# t1-power3.net
KiCad netlist of a schematic drawn in Altium Designer
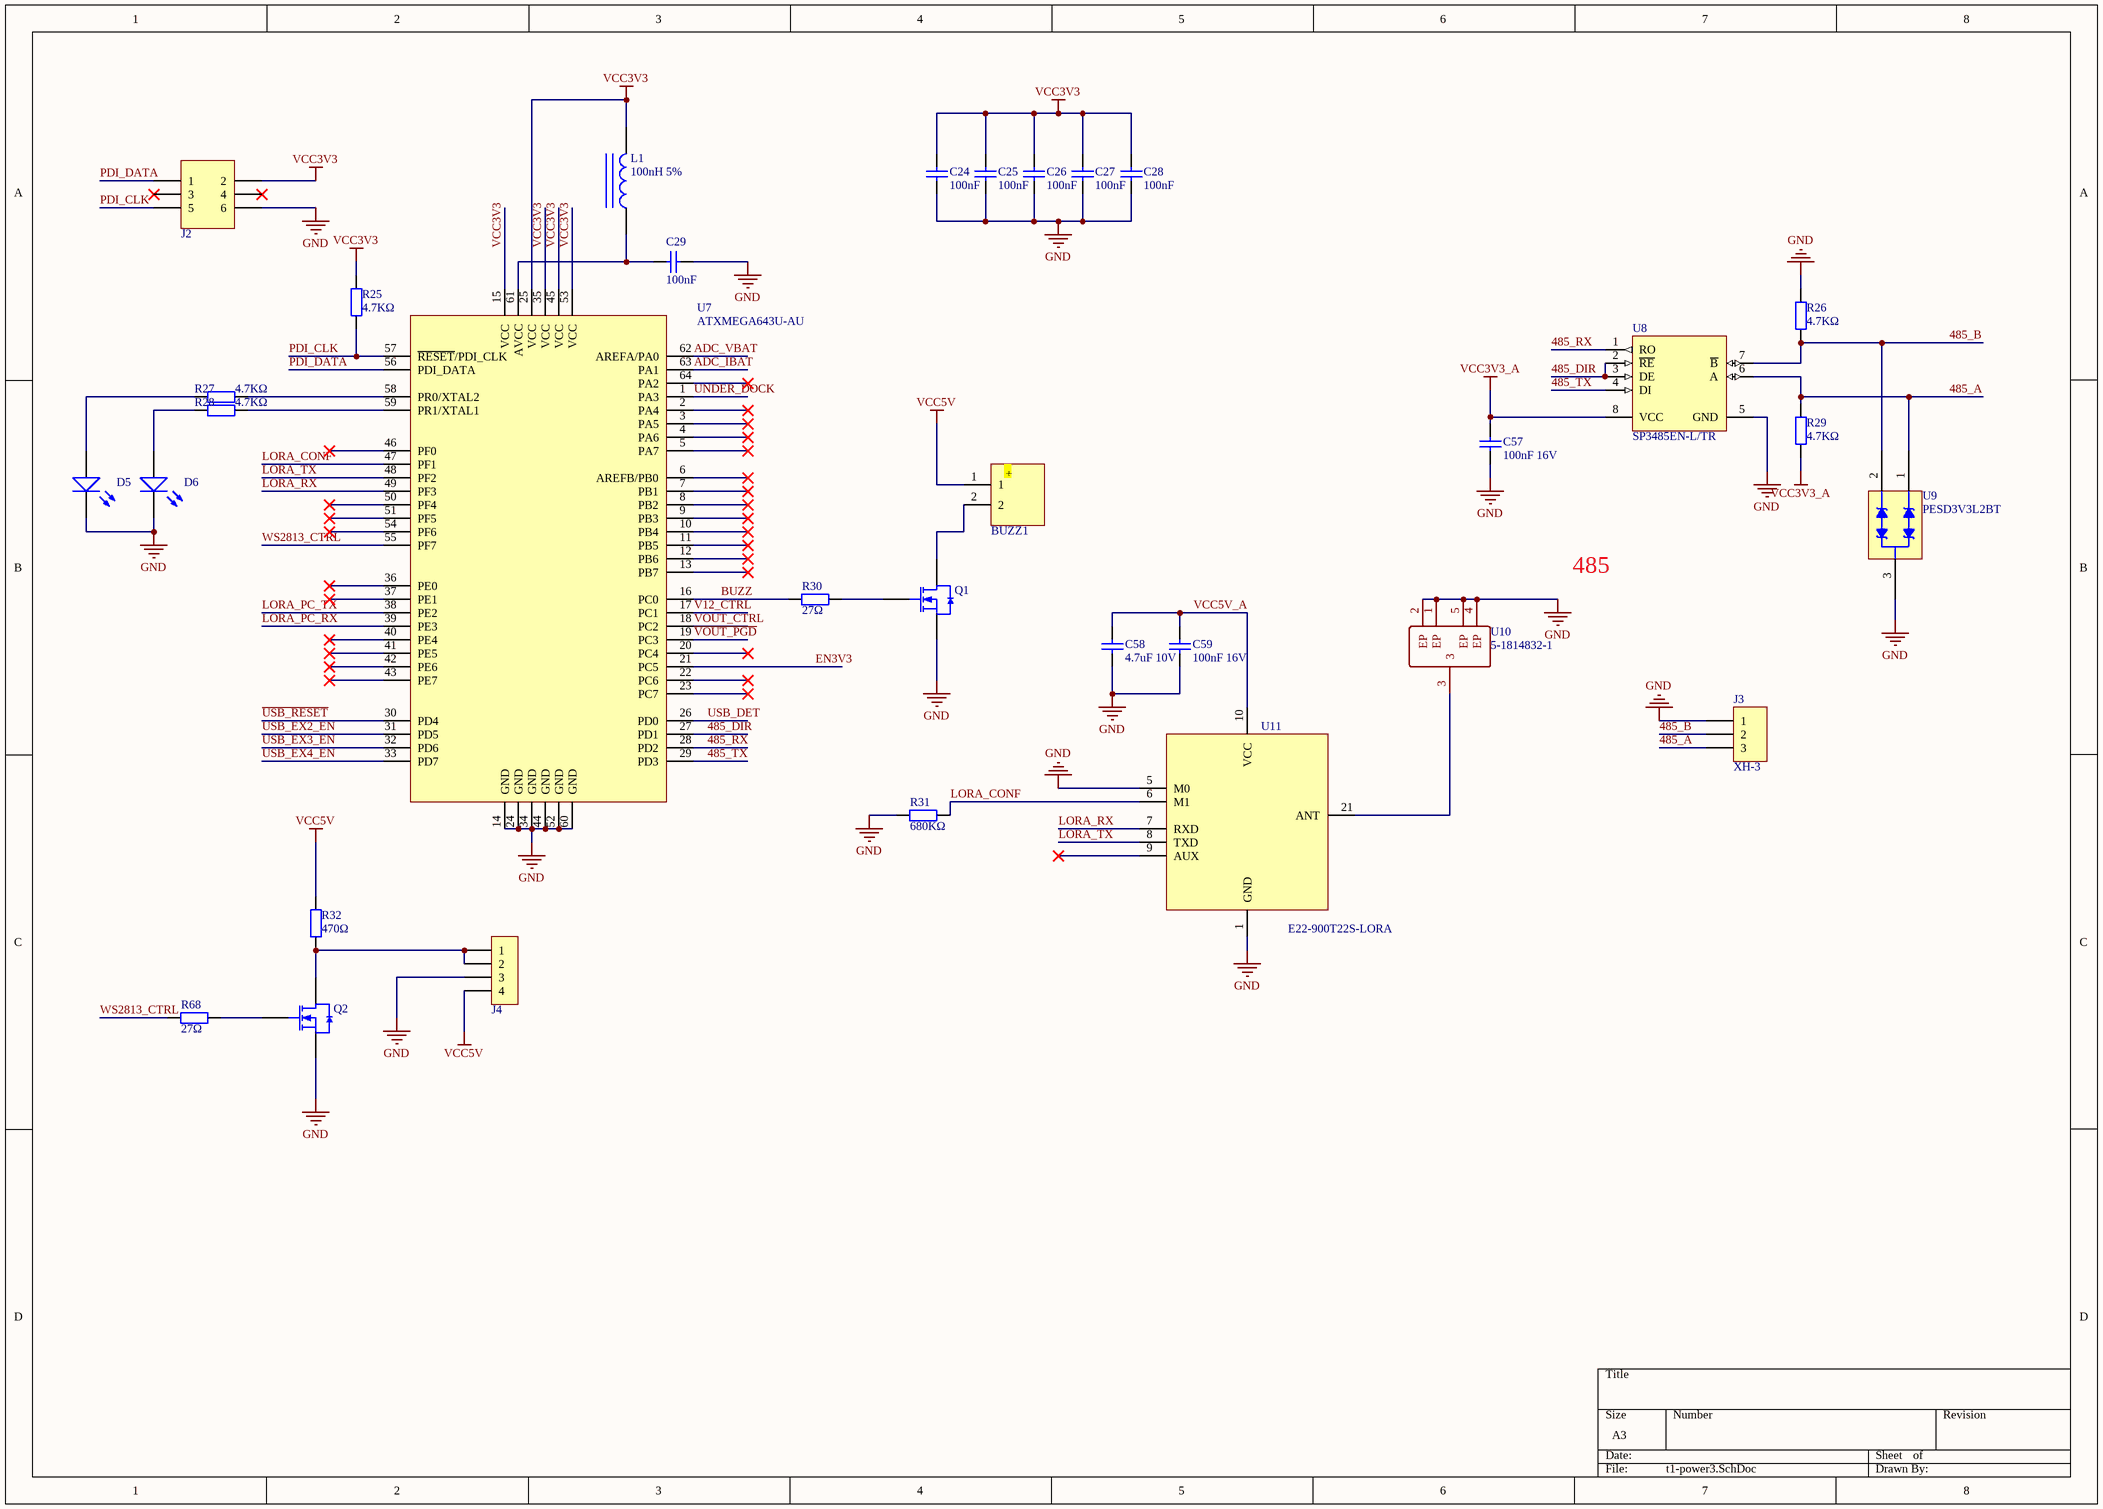
[diagram p0: t1-power3.SchDoc]

(export (version "E")
  (design (tool "Eeschema 10.0.6"))
  (components
    (comp (ref "BUZZ1") (value "B?") (footprint "直插5.0_9*5.5mm") (libsource (lib "我的原理图库") (part "BUZZ")))
    (comp (ref "C24")
      (value "100nF")
      (footprint "0402_C")
      (description "贴片电容")
      (libsource (lib "AD封装2018.9.19Miscellaneous Devices LC") (part "0402 100nF (104) 10% 16V"))
    )
    (comp (ref "C25")
      (value "100nF")
      (footprint "0402_C")
      (description "贴片电容")
      (libsource (lib "AD封装2018.9.19Miscellaneous Devices LC") (part "0402 100nF (104) 10% 16V"))
    )
    (comp (ref "C26")
      (value "100nF")
      (footprint "0402_C")
      (description "贴片电容")
      (libsource (lib "AD封装2018.9.19Miscellaneous Devices LC") (part "0402 100nF (104) 10% 16V"))
    )
    (comp (ref "C27")
      (value "100nF")
      (footprint "0402_C")
      (description "贴片电容")
      (libsource (lib "AD封装2018.9.19Miscellaneous Devices LC") (part "0402 100nF (104) 10% 16V"))
    )
    (comp (ref "C28")
      (value "100nF")
      (footprint "0402_C")
      (description "贴片电容")
      (libsource (lib "AD封装2018.9.19Miscellaneous Devices LC") (part "0402 100nF (104) 10% 16V"))
    )
    (comp (ref "C29")
      (value "100nF")
      (footprint "0402_C")
      (description "贴片电容")
      (libsource (lib "AD封装2018.9.19Miscellaneous Devices LC") (part "0402 100nF (104) 10% 16V"))
    )
    (comp (ref "C57")
      (value "100nF 16V")
      (footprint "0402_C")
      (description "贴片电容")
      (libsource (lib "AD封装2018.9.19Miscellaneous Devices LC") (part "0402 100nF (104) 10% 16V"))
    )
    (comp (ref "C58")
      (value "4.7uF 10V")
      (footprint "0402_C")
      (description "贴片电容")
      (libsource (lib "AD封装2018.9.19Miscellaneous Devices LC") (part "0402 4.7uF (475) 20% 10V"))
    )
    (comp (ref "C59")
      (value "100nF 16V")
      (footprint "0402_C")
      (description "贴片电容")
      (libsource (lib "AD封装2018.9.19Miscellaneous Devices LC") (part "0402 100nF (104) 10% 16V"))
    )
    (comp (ref "D5")
      (value "白灯 0603")
      (footprint "0603_LED_S1")
      (description "发光二极管")
      (libsource (lib "AD封装2018.9.19Miscellaneous Devices LC") (part "0603 白灯"))
    )
    (comp (ref "D6")
      (value "白灯 0603")
      (footprint "0603_LED_S1")
      (description "发光二极管")
      (libsource (lib "AD封装2018.9.19Miscellaneous Devices LC") (part "0603 白灯"))
    )
    (comp (ref "J2")
      (value "Conn_02*03_2.54mm")
      (footprint "排针2.54mm")
      (libsource (lib "我的集成库") (part "Conn_02*03_2.54mm"))
    )
    (comp (ref "J3") (value "XH-3") (footprint "ph3-2.0") (libsource (lib "我的原理图库") (part "XH-3")))
    (comp (ref "J4") (value "header4") (footprint "xh-4") (libsource (lib "我的集成库") (part "header4")))
    (comp (ref "L1")
      (value "100nH 5%")
      (footprint "0402_L")
      (description "贴片电感")
      (libsource (lib "AD封装2018.9.19Miscellaneous Devices LC") (part "0402 10nH 5%"))
    )
    (comp (ref "Q1")
      (value "AO3400A N道沟 X0YV1T SOT-23")
      (footprint "SOT-23-3L")
      (description "MOS(场效应管)")
      (libsource (lib "AD封装2018.9.19Miscellaneous Devices LC") (part "AO3400A N道沟 X0YV1T SOT-23"))
    )
    (comp (ref "Q2")
      (value "AO3400A N道沟 X0YV1T SOT-23")
      (footprint "SOT-23-3L")
      (description "MOS(场效应管)")
      (libsource (lib "AD封装2018.9.19Miscellaneous Devices LC") (part "AO3400A N道沟 X0YV1T SOT-23"))
    )
    (comp (ref "R25")
      (value "4.7KΩ")
      (footprint "0402_R")
      (description "贴片电阻")
      (libsource (lib "AD封装2018.9.19Miscellaneous Devices LC") (part "0402 4.7KΩ (4701) 1%"))
    )
    (comp (ref "R26")
      (value "4.7KΩ")
      (footprint "0402_R")
      (description "贴片电阻")
      (libsource (lib "AD封装2018.9.19Miscellaneous Devices LC") (part "0402 4.7KΩ (4701) 1%"))
    )
    (comp (ref "R27")
      (value "4.7KΩ")
      (footprint "0402_R")
      (description "贴片电阻")
      (libsource (lib "") (part "0402 4.7KΩ (4701) 1%_1"))
    )
    (comp (ref "R28")
      (value "4.7KΩ")
      (footprint "0402_R")
      (description "贴片电阻")
      (libsource (lib "") (part "0402 4.7KΩ (4701) 1%_1"))
    )
    (comp (ref "R29")
      (value "4.7KΩ")
      (footprint "0402_R")
      (description "贴片电阻")
      (libsource (lib "AD封装2018.9.19Miscellaneous Devices LC") (part "0402 4.7KΩ (4701) 1%"))
    )
    (comp (ref "R30")
      (value "27Ω")
      (footprint "0402_R")
      (description "贴片电阻")
      (libsource (lib "AD封装2018.9.19Miscellaneous Devices LC") (part "0402 27KΩ (2702) 1%"))
    )
    (comp (ref "R31")
      (value "680KΩ")
      (footprint "0402_R")
      (description "贴片电阻")
      (libsource (lib "AD封装2018.9.19Miscellaneous Devices LC") (part "0402 680Ω (6800) 1%"))
    )
    (comp (ref "R32")
      (value "470Ω")
      (footprint "0402_R")
      (description "贴片电阻")
      (libsource (lib "AD封装2018.9.19Miscellaneous Devices LC") (part "0402 470Ω (4700) 1%"))
    )
    (comp (ref "R68")
      (value "27Ω")
      (footprint "0402_R")
      (description "贴片电阻")
      (libsource (lib "AD封装2018.9.19Miscellaneous Devices LC") (part "0402 27KΩ (2702) 1%"))
    )
    (comp (ref "U7")
      (value "ATXMEGA643U-AU")
      (footprint "TQFP-64_14*14*08P")
      (description "TFQP-64")
      (libsource (lib "我的原理图库") (part "atxmage64a3u"))
    )
    (comp (ref "U8")
      (value "SP3485EN-L/TR")
      (footprint "SOIC-8_150mil")
      (description "RS-485/RS-422")
      (libsource (lib "IC") (part "SP3485EN-L/TR_[C8963]"))
    )
    (comp (ref "U9")
      (value "PESD3V3L2BT")
      (footprint "SOT-23(SOT-23-3)")
      (description "TVS")
      (libsource (lib "AD封装2018.9.19Miscellaneous Devices LC") (part "PSM712-LF-T7_[C32677]"))
    )
    (comp (ref "U10")
      (value "5-1814832-1")
      (footprint "SMA 连接器")
      (libsource (lib "我的集成库") (part "5-1814832-1"))
    )
    (comp (ref "U11")
      (value "E22-900T22S-LORA")
      (footprint "LORA-16mmX26mm")
      (libsource (lib "我的集成库") (part "E22-900T22S-LORA"))
    )
  )
  (nets
    (net (code "1") (name "/485_A") (class "Default")
      (node (ref "J3") (pin "3") (pinfunction "3_3") (pintype "passive"))
      (node (ref "R29") (pin "2") (pinfunction "2_2") (pintype "passive"))
      (node (ref "U8") (pin "6") (pinfunction "A_6") (pintype "bidirectional"))
      (node (ref "U9") (pin "1") (pinfunction "1_1") (pintype "passive"))
    )
    (net (code "2") (name "/485_B") (class "Default")
      (node (ref "J3") (pin "2") (pinfunction "2_2") (pintype "passive"))
      (node (ref "R26") (pin "1") (pinfunction "1_1") (pintype "passive"))
      (node (ref "U8") (pin "7") (pinfunction "~{B}_7") (pintype "bidirectional"))
      (node (ref "U9") (pin "2") (pinfunction "2_2") (pintype "passive"))
    )
    (net (code "3") (name "/485_DIR") (class "Default")
      (node (ref "U7") (pin "27") (pinfunction "PD1_27") (pintype "passive"))
      (node (ref "U8") (pin "2") (pinfunction "~{RE}_2") (pintype "input"))
      (node (ref "U8") (pin "3") (pinfunction "DE_3") (pintype "input"))
    )
    (net (code "4") (name "/485_RX") (class "Default")
      (node (ref "U7") (pin "28") (pinfunction "PD2_28") (pintype "passive"))
      (node (ref "U8") (pin "1") (pinfunction "RO_1") (pintype "output"))
    )
    (net (code "5") (name "/485_TX") (class "Default")
      (node (ref "U7") (pin "29") (pinfunction "PD3_29") (pintype "passive"))
      (node (ref "U8") (pin "4") (pinfunction "DI_4") (pintype "input"))
    )
    (net (code "6") (name "/ADC_IBAT") (class "Default")
      (node (ref "U7") (pin "63") (pinfunction "PA1_63") (pintype "passive"))
    )
    (net (code "7") (name "/ADC_VBAT") (class "Default")
      (node (ref "U7") (pin "62") (pinfunction "AREFA/PA0_62") (pintype "passive"))
    )
    (net (code "8") (name "/BUZZ") (class "Default")
      (node (ref "R30") (pin "1") (pinfunction "1_1") (pintype "passive"))
      (node (ref "U7") (pin "16") (pinfunction "PC0_16") (pintype "passive"))
    )
    (net (code "9") (name "/EN3V3") (class "Default")
      (node (ref "U7") (pin "21") (pinfunction "PC5_21") (pintype "passive"))
    )
    (net (code "10") (name "/LORA_CONF") (class "Default")
      (node (ref "R31") (pin "2") (pinfunction "2_2") (pintype "passive"))
      (node (ref "U11") (pin "6") (pinfunction "M1_6") (pintype "passive"))
      (node (ref "U7") (pin "47") (pinfunction "PF1_47") (pintype "passive"))
    )
    (net (code "11") (name "/LORA_PC_RX") (class "Default")
      (node (ref "U7") (pin "39") (pinfunction "PE3_39") (pintype "passive"))
    )
    (net (code "12") (name "/LORA_PC_TX") (class "Default")
      (node (ref "U7") (pin "38") (pinfunction "PE2_38") (pintype "passive"))
    )
    (net (code "13") (name "/LORA_RX") (class "Default")
      (node (ref "U11") (pin "7") (pinfunction "RXD_7") (pintype "passive"))
      (node (ref "U7") (pin "49") (pinfunction "PF3_49") (pintype "passive"))
    )
    (net (code "14") (name "/LORA_TX") (class "Default")
      (node (ref "U11") (pin "8") (pinfunction "TXD_8") (pintype "passive"))
      (node (ref "U7") (pin "48") (pinfunction "PF2_48") (pintype "passive"))
    )
    (net (code "15") (name "/PDI_CLK") (class "Default")
      (node (ref "J2") (pin "5") (pinfunction "5_5") (pintype "passive"))
      (node (ref "R25") (pin "1") (pinfunction "1_1") (pintype "passive"))
      (node (ref "U7") (pin "57") (pinfunction "~{RESET}/PDI_CLK_57") (pintype "passive"))
    )
    (net (code "16") (name "/PDI_DATA") (class "Default")
      (node (ref "J2") (pin "1") (pinfunction "1_1") (pintype "passive"))
      (node (ref "U7") (pin "56") (pinfunction "PDI_DATA_56") (pintype "passive"))
    )
    (net (code "17") (name "/UNDER_DOCK") (class "Default")
      (node (ref "U7") (pin "1") (pinfunction "PA3_1") (pintype "passive"))
    )
    (net (code "18") (name "/USB_DET") (class "Default")
      (node (ref "U7") (pin "26") (pinfunction "PD0_26") (pintype "passive"))
    )
    (net (code "19") (name "/USB_EX2_EN") (class "Default")
      (node (ref "U7") (pin "31") (pinfunction "PD5_31") (pintype "passive"))
    )
    (net (code "20") (name "/USB_EX3_EN") (class "Default")
      (node (ref "U7") (pin "32") (pinfunction "PD6_32") (pintype "passive"))
    )
    (net (code "21") (name "/USB_EX4_EN") (class "Default")
      (node (ref "U7") (pin "33") (pinfunction "PD7_33") (pintype "passive"))
    )
    (net (code "22") (name "/V12_CTRL") (class "Default")
      (node (ref "U7") (pin "17") (pinfunction "PC1_17") (pintype "passive"))
    )
    (net (code "23") (name "/VCC5V_A") (class "Default")
      (node (ref "C58") (pin "2") (pinfunction "2_2") (pintype "passive"))
      (node (ref "C59") (pin "2") (pinfunction "2_2") (pintype "passive"))
      (node (ref "U11") (pin "10") (pinfunction "VCC_10") (pintype "passive"))
    )
    (net (code "24") (name "/VOUT_CTRL") (class "Default")
      (node (ref "U7") (pin "18") (pinfunction "PC2_18") (pintype "passive"))
    )
    (net (code "25") (name "/WS2813_CTRL") (class "Default")
      (node (ref "R68") (pin "1") (pinfunction "1_1") (pintype "passive"))
      (node (ref "U7") (pin "55") (pinfunction "PF7_55") (pintype "passive"))
    )
    (net (code "26") (name "/~{USB_RESET}") (class "Default")
      (node (ref "U7") (pin "30") (pinfunction "PD4_30") (pintype "passive"))
    )
    (net (code "27") (name "/~{VOUT_PGD}") (class "Default")
      (node (ref "U7") (pin "19") (pinfunction "PC3_19") (pintype "passive"))
    )
    (net (code "28") (name "GND") (class "Default")
      (node (ref "C24") (pin "1") (pinfunction "1_1") (pintype "passive"))
      (node (ref "C25") (pin "1") (pinfunction "1_1") (pintype "passive"))
      (node (ref "C26") (pin "1") (pinfunction "1_1") (pintype "passive"))
      (node (ref "C27") (pin "1") (pinfunction "1_1") (pintype "passive"))
      (node (ref "C28") (pin "1") (pinfunction "1_1") (pintype "passive"))
      (node (ref "C29") (pin "2") (pinfunction "2_2") (pintype "passive"))
      (node (ref "C57") (pin "1") (pinfunction "1_1") (pintype "passive"))
      (node (ref "C58") (pin "1") (pinfunction "1_1") (pintype "passive"))
      (node (ref "C59") (pin "1") (pinfunction "1_1") (pintype "passive"))
      (node (ref "D5") (pin "K") (pinfunction "K_K") (pintype "passive"))
      (node (ref "D6") (pin "K") (pinfunction "K_K") (pintype "passive"))
      (node (ref "J2") (pin "6") (pinfunction "6_6") (pintype "passive"))
      (node (ref "J3") (pin "1") (pinfunction "1_1") (pintype "passive"))
      (node (ref "J4") (pin "3") (pinfunction "3_3") (pintype "passive"))
      (node (ref "Q1") (pin "2") (pinfunction "S_2") (pintype "passive"))
      (node (ref "Q2") (pin "2") (pinfunction "S_2") (pintype "passive"))
      (node (ref "R26") (pin "2") (pinfunction "2_2") (pintype "passive"))
      (node (ref "R31") (pin "1") (pinfunction "1_1") (pintype "passive"))
      (node (ref "U10") (pin "1") (pinfunction "EP_1") (pintype "passive"))
      (node (ref "U10") (pin "2") (pinfunction "EP_2") (pintype "passive"))
      (node (ref "U10") (pin "4") (pinfunction "EP_4") (pintype "passive"))
      (node (ref "U10") (pin "5") (pinfunction "EP_5") (pintype "passive"))
      (node (ref "U11") (pin "1") (pinfunction "GND_1") (pintype "passive"))
      (node (ref "U11") (pin "5") (pinfunction "M0_5") (pintype "passive"))
      (node (ref "U7") (pin "14") (pinfunction "GND_14") (pintype "passive"))
      (node (ref "U7") (pin "24") (pinfunction "GND_24") (pintype "passive"))
      (node (ref "U7") (pin "34") (pinfunction "GND_34") (pintype "passive"))
      (node (ref "U7") (pin "44") (pinfunction "GND_44") (pintype "passive"))
      (node (ref "U7") (pin "52") (pinfunction "GND_52") (pintype "passive"))
      (node (ref "U7") (pin "60") (pinfunction "GND_60") (pintype "passive"))
      (node (ref "U8") (pin "5") (pinfunction "GND_5") (pintype "power_in"))
      (node (ref "U9") (pin "3") (pinfunction "3_3") (pintype "passive"))
    )
    (net (code "29") (name "Net-(D5-PadA)") (class "Default")
      (node (ref "D5") (pin "A") (pinfunction "A_A") (pintype "passive"))
      (node (ref "R27") (pin "1") (pinfunction "1_1") (pintype "passive"))
    )
    (net (code "30") (name "Net-(D6-PadA)") (class "Default")
      (node (ref "D6") (pin "A") (pinfunction "A_A") (pintype "passive"))
      (node (ref "R28") (pin "1") (pinfunction "1_1") (pintype "passive"))
    )
    (net (code "31") (name "Net-(Q1-D)") (class "Default")
      (node (ref "BUZZ1") (pin "2") (pinfunction "2_2") (pintype "passive"))
      (node (ref "Q1") (pin "3") (pinfunction "D_3") (pintype "passive"))
    )
    (net (code "32") (name "Net-(Q1-G)") (class "Default")
      (node (ref "Q1") (pin "1") (pinfunction "G_1") (pintype "passive"))
      (node (ref "R30") (pin "2") (pinfunction "2_2") (pintype "passive"))
    )
    (net (code "33") (name "Net-(Q2-D)") (class "Default")
      (node (ref "J4") (pin "1") (pinfunction "1_1") (pintype "passive"))
      (node (ref "J4") (pin "2") (pinfunction "2_2") (pintype "passive"))
      (node (ref "Q2") (pin "3") (pinfunction "D_3") (pintype "passive"))
      (node (ref "R32") (pin "1") (pinfunction "1_1") (pintype "passive"))
    )
    (net (code "34") (name "Net-(Q2-G)") (class "Default")
      (node (ref "Q2") (pin "1") (pinfunction "G_1") (pintype "passive"))
      (node (ref "R68") (pin "2") (pinfunction "2_2") (pintype "passive"))
    )
    (net (code "35") (name "Net-(U7-AVCC)") (class "Default")
      (node (ref "C29") (pin "1") (pinfunction "1_1") (pintype "passive"))
      (node (ref "L1") (pin "1") (pinfunction "1_1") (pintype "passive"))
      (node (ref "U7") (pin "61") (pinfunction "AVCC_61") (pintype "passive"))
    )
    (net (code "36") (name "Net-(U7-PR0{slash}XTAL2)") (class "Default")
      (node (ref "R27") (pin "2") (pinfunction "2_2") (pintype "passive"))
      (node (ref "U7") (pin "58") (pinfunction "PR0/XTAL2_58") (pintype "passive"))
    )
    (net (code "37") (name "Net-(U7-PR1{slash}XTAL1)") (class "Default")
      (node (ref "R28") (pin "2") (pinfunction "2_2") (pintype "passive"))
      (node (ref "U7") (pin "59") (pinfunction "PR1/XTAL1_59") (pintype "passive"))
    )
    (net (code "38") (name "Net-(U11-ANT)") (class "Default")
      (node (ref "U10") (pin "3") (pinfunction "3_3") (pintype "passive"))
      (node (ref "U11") (pin "21") (pinfunction "ANT_21") (pintype "passive"))
    )
    (net (code "39") (name "VCC3V3") (class "Default")
      (node (ref "C24") (pin "2") (pinfunction "2_2") (pintype "passive"))
      (node (ref "C25") (pin "2") (pinfunction "2_2") (pintype "passive"))
      (node (ref "C26") (pin "2") (pinfunction "2_2") (pintype "passive"))
      (node (ref "C27") (pin "2") (pinfunction "2_2") (pintype "passive"))
      (node (ref "C28") (pin "2") (pinfunction "2_2") (pintype "passive"))
      (node (ref "J2") (pin "2") (pinfunction "2_2") (pintype "passive"))
      (node (ref "L1") (pin "2") (pinfunction "2_2") (pintype "passive"))
      (node (ref "R25") (pin "2") (pinfunction "2_2") (pintype "passive"))
      (node (ref "U7") (pin "15") (pinfunction "VCC_15") (pintype "passive"))
      (node (ref "U7") (pin "25") (pinfunction "VCC_25") (pintype "passive"))
      (node (ref "U7") (pin "35") (pinfunction "VCC_35") (pintype "passive"))
      (node (ref "U7") (pin "45") (pinfunction "VCC_45") (pintype "passive"))
      (node (ref "U7") (pin "53") (pinfunction "VCC_53") (pintype "passive"))
    )
    (net (code "40") (name "VCC3V3_A") (class "Default")
      (node (ref "C57") (pin "2") (pinfunction "2_2") (pintype "passive"))
      (node (ref "R29") (pin "1") (pinfunction "1_1") (pintype "passive"))
      (node (ref "U8") (pin "8") (pinfunction "VCC_8") (pintype "power_in"))
    )
    (net (code "41") (name "VCC5V") (class "Default")
      (node (ref "BUZZ1") (pin "1") (pinfunction "1_1") (pintype "passive"))
      (node (ref "J4") (pin "4") (pinfunction "4_4") (pintype "passive"))
      (node (ref "R32") (pin "2") (pinfunction "2_2") (pintype "passive"))
    )
    (net (code "42") (name "unconnected-(J2-Pad3)") (class "Default")
      (node (ref "J2") (pin "3") (pinfunction "3_3") (pintype "passive+no_connect"))
    )
    (net (code "43") (name "unconnected-(J2-Pad4)") (class "Default")
      (node (ref "J2") (pin "4") (pinfunction "4_4") (pintype "passive+no_connect"))
    )
    (net (code "44") (name "unconnected-(U7-AREFB{slash}PB0-Pad6)") (class "Default")
      (node (ref "U7") (pin "6") (pinfunction "AREFB/PB0_6") (pintype "passive+no_connect"))
    )
    (net (code "45") (name "unconnected-(U7-PA2-Pad64)") (class "Default")
      (node (ref "U7") (pin "64") (pinfunction "PA2_64") (pintype "passive+no_connect"))
    )
    (net (code "46") (name "unconnected-(U7-PA4-Pad2)") (class "Default")
      (node (ref "U7") (pin "2") (pinfunction "PA4_2") (pintype "passive+no_connect"))
    )
    (net (code "47") (name "unconnected-(U7-PA5-Pad3)") (class "Default")
      (node (ref "U7") (pin "3") (pinfunction "PA5_3") (pintype "passive+no_connect"))
    )
    (net (code "48") (name "unconnected-(U7-PA6-Pad4)") (class "Default")
      (node (ref "U7") (pin "4") (pinfunction "PA6_4") (pintype "passive+no_connect"))
    )
    (net (code "49") (name "unconnected-(U7-PA7-Pad5)") (class "Default")
      (node (ref "U7") (pin "5") (pinfunction "PA7_5") (pintype "passive+no_connect"))
    )
    (net (code "50") (name "unconnected-(U7-PB1-Pad7)") (class "Default")
      (node (ref "U7") (pin "7") (pinfunction "PB1_7") (pintype "passive+no_connect"))
    )
    (net (code "51") (name "unconnected-(U7-PB2-Pad8)") (class "Default")
      (node (ref "U7") (pin "8") (pinfunction "PB2_8") (pintype "passive+no_connect"))
    )
    (net (code "52") (name "unconnected-(U7-PB3-Pad9)") (class "Default")
      (node (ref "U7") (pin "9") (pinfunction "PB3_9") (pintype "passive+no_connect"))
    )
    (net (code "53") (name "unconnected-(U7-PB4-Pad10)") (class "Default")
      (node (ref "U7") (pin "10") (pinfunction "PB4_10") (pintype "passive+no_connect"))
    )
    (net (code "54") (name "unconnected-(U7-PB5-Pad11)") (class "Default")
      (node (ref "U7") (pin "11") (pinfunction "PB5_11") (pintype "passive+no_connect"))
    )
    (net (code "55") (name "unconnected-(U7-PB6-Pad12)") (class "Default")
      (node (ref "U7") (pin "12") (pinfunction "PB6_12") (pintype "passive+no_connect"))
    )
    (net (code "56") (name "unconnected-(U7-PB7-Pad13)") (class "Default")
      (node (ref "U7") (pin "13") (pinfunction "PB7_13") (pintype "passive+no_connect"))
    )
    (net (code "57") (name "unconnected-(U7-PC4-Pad20)") (class "Default")
      (node (ref "U7") (pin "20") (pinfunction "PC4_20") (pintype "passive+no_connect"))
    )
    (net (code "58") (name "unconnected-(U7-PC6-Pad22)") (class "Default")
      (node (ref "U7") (pin "22") (pinfunction "PC6_22") (pintype "passive+no_connect"))
    )
    (net (code "59") (name "unconnected-(U7-PC7-Pad23)") (class "Default")
      (node (ref "U7") (pin "23") (pinfunction "PC7_23") (pintype "passive+no_connect"))
    )
    (net (code "60") (name "unconnected-(U7-PE0-Pad36)") (class "Default")
      (node (ref "U7") (pin "36") (pinfunction "PE0_36") (pintype "passive+no_connect"))
    )
    (net (code "61") (name "unconnected-(U7-PE1-Pad37)") (class "Default")
      (node (ref "U7") (pin "37") (pinfunction "PE1_37") (pintype "passive+no_connect"))
    )
    (net (code "62") (name "unconnected-(U7-PE4-Pad40)") (class "Default")
      (node (ref "U7") (pin "40") (pinfunction "PE4_40") (pintype "passive+no_connect"))
    )
    (net (code "63") (name "unconnected-(U7-PE5-Pad41)") (class "Default")
      (node (ref "U7") (pin "41") (pinfunction "PE5_41") (pintype "passive+no_connect"))
    )
    (net (code "64") (name "unconnected-(U7-PE6-Pad42)") (class "Default")
      (node (ref "U7") (pin "42") (pinfunction "PE6_42") (pintype "passive+no_connect"))
    )
    (net (code "65") (name "unconnected-(U7-PE7-Pad43)") (class "Default")
      (node (ref "U7") (pin "43") (pinfunction "PE7_43") (pintype "passive+no_connect"))
    )
    (net (code "66") (name "unconnected-(U7-PF0-Pad46)") (class "Default")
      (node (ref "U7") (pin "46") (pinfunction "PF0_46") (pintype "passive+no_connect"))
    )
    (net (code "67") (name "unconnected-(U7-PF4-Pad50)") (class "Default")
      (node (ref "U7") (pin "50") (pinfunction "PF4_50") (pintype "passive+no_connect"))
    )
    (net (code "68") (name "unconnected-(U7-PF5-Pad51)") (class "Default")
      (node (ref "U7") (pin "51") (pinfunction "PF5_51") (pintype "passive+no_connect"))
    )
    (net (code "69") (name "unconnected-(U7-PF6-Pad54)") (class "Default")
      (node (ref "U7") (pin "54") (pinfunction "PF6_54") (pintype "passive+no_connect"))
    )
    (net (code "70") (name "unconnected-(U11-AUX-Pad9)") (class "Default")
      (node (ref "U11") (pin "9") (pinfunction "AUX_9") (pintype "passive+no_connect"))
    )
  )
)
